# top_power.net
KiCad netlist of a schematic drawn in Altium Designer
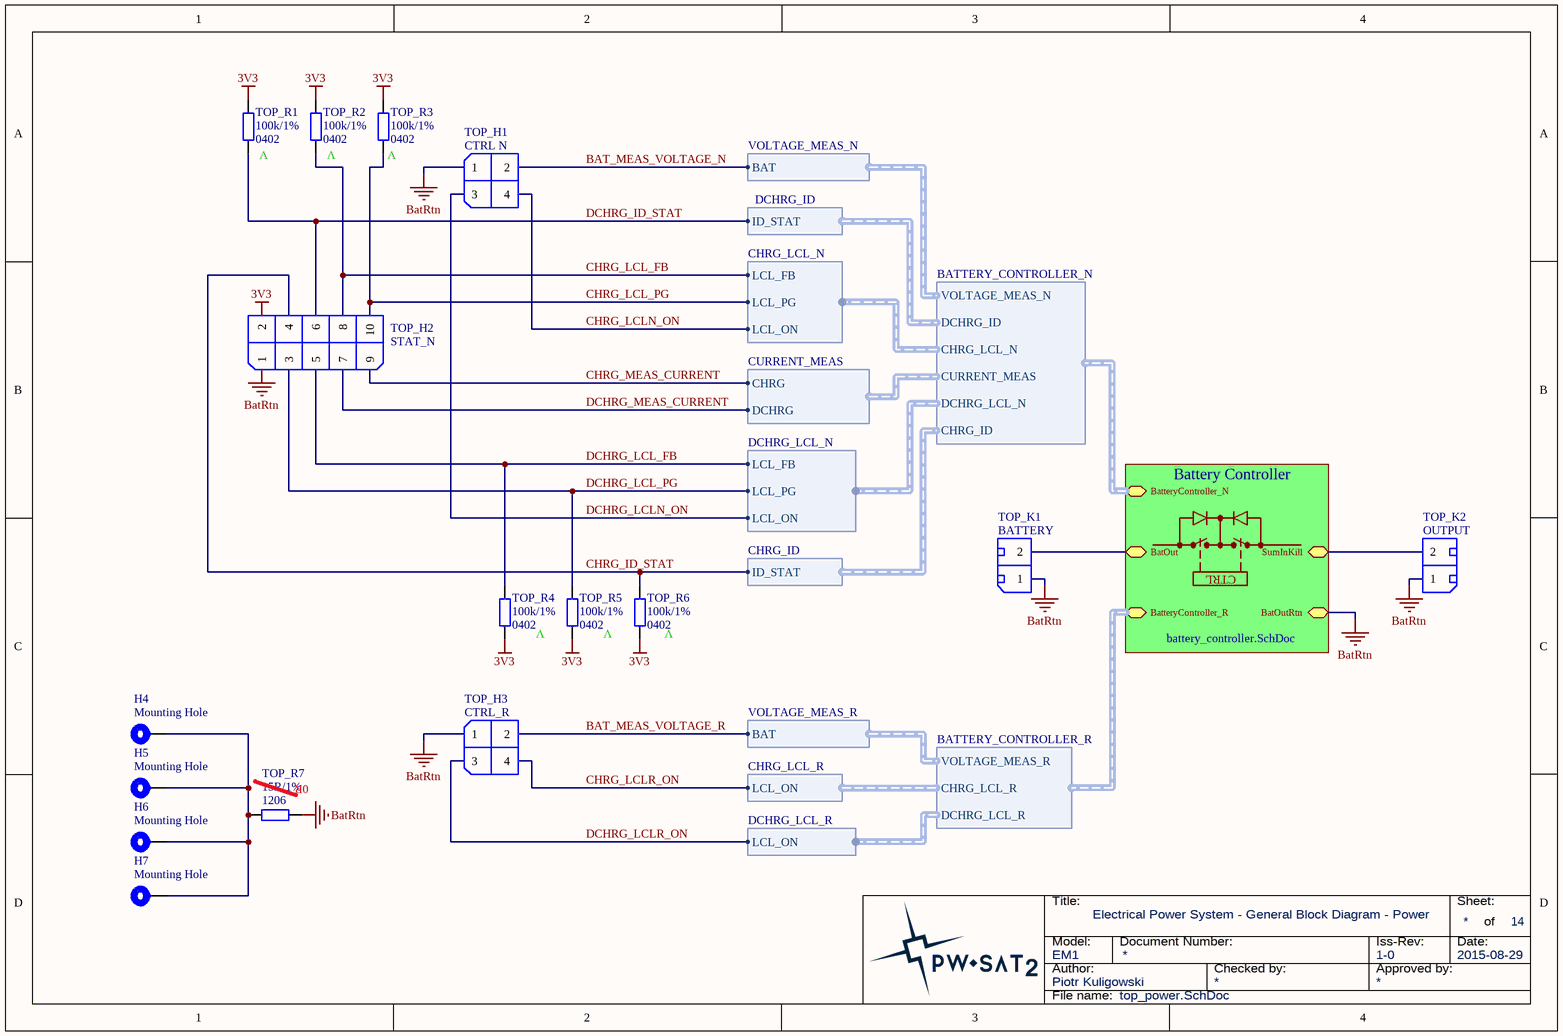
[diagram p0: top_power.SchDoc]

(export (version "E")
  (design (tool "Eeschema 10.0.6"))
  (components
    (comp (ref "H4")
      (value "Mounting Hole")
      (footprint "PC-104_PcbMntHole_M3")
      (description "PCB Mounting Hole")
      (libsource (lib "connectors_printed-circuit-board") (part "MntHole"))
    )
    (comp (ref "H5")
      (value "Mounting Hole")
      (footprint "PC-104_PcbMntHole_M3")
      (description "PCB Mounting Hole")
      (libsource (lib "connectors_printed-circuit-board") (part "MntHole"))
    )
    (comp (ref "H6")
      (value "Mounting Hole")
      (footprint "PC-104_PcbMntHole_M3")
      (description "PCB Mounting Hole")
      (libsource (lib "connectors_printed-circuit-board") (part "MntHole"))
    )
    (comp (ref "H7")
      (value "Mounting Hole")
      (footprint "PC-104_PcbMntHole_M3")
      (description "PCB Mounting Hole")
      (libsource (lib "connectors_printed-circuit-board") (part "MntHole"))
    )
    (comp (ref "TOP_H1")
      (value "CTRL N")
      (footprint "Harwin_Datamate_L-Tek_M80-8670405")
      (description "Harwin DataMate L-Tek, 2mm pitch, 2x2pin.")
      (libsource (lib "connectors_printed-circuit-board") (part "Harwin_Datamate_L-Tek_2x2pin"))
    )
    (comp (ref "TOP_H2")
      (value "STAT_N")
      (footprint "Harwin_Datamate_L-Tek_M80-8671005")
      (description "Harwin DataMate L-Tek, 2mm pitch, 2x5pin.")
      (libsource (lib "connectors_printed-circuit-board") (part "Harwin_Datamate_L-Tek_2x5pin"))
    )
    (comp (ref "TOP_H3")
      (value "CTRL_R")
      (footprint "Harwin_Datamate_L-Tek_M80-8670405")
      (description "Harwin DataMate L-Tek, 2mm pitch, 2x2pin.")
      (libsource (lib "connectors_printed-circuit-board") (part "Harwin_Datamate_L-Tek_2x2pin"))
    )
    (comp (ref "TOP_K1")
      (value "TB-2.5-PD-xx")
      (footprint "TerminalBlock_Spring_2.54_2-R")
      (description "Terminal block with spring, 2-pin, 2.54mm pitch, right angle.")
      (fields (field (name "PROVIDERPARTNUMBER") "BATTERY") (field (name "PROVIDER") "TME.eu"))
      (libsource (lib "connectors_printed-circuit-board") (part "TerminalBlock_Spring_2.54_2-R"))
    )
    (comp (ref "TOP_K2")
      (value "TB-2.5-PD-xx")
      (footprint "TerminalBlock_Spring_2.54_2-R")
      (description "Terminal block with spring, 2-pin, 2.54mm pitch, right angle.")
      (fields (field (name "PROVIDERPARTNUMBER") "OUTPUT") (field (name "PROVIDER") "TME.eu"))
      (libsource (lib "connectors_printed-circuit-board") (part "TerminalBlock_Spring_2.54_2-R"))
    )
    (comp (ref "TOP_R1")
      (value "100k/1%")
      (footprint "SMD_Resistor_0402")
      (description "100k/1% Vishay CRCW 0402 Resistor. 63mW, 100ppm, 50V.")
      (fields (field (name "MANUFACTURER") "Vishay") (field (name "PACKAGE") "0402"))
      (libsource (lib "resistors") (part "CRCW0402100KFKxxxx"))
    )
    (comp (ref "TOP_R2")
      (value "100k/1%")
      (footprint "SMD_Resistor_0402")
      (description "100k/1% Vishay CRCW 0402 Resistor. 63mW, 100ppm, 50V.")
      (fields (field (name "MANUFACTURER") "Vishay") (field (name "PACKAGE") "0402"))
      (libsource (lib "resistors") (part "CRCW0402100KFKxxxx"))
    )
    (comp (ref "TOP_R3")
      (value "100k/1%")
      (footprint "SMD_Resistor_0402")
      (description "100k/1% Vishay CRCW 0402 Resistor. 63mW, 100ppm, 50V.")
      (fields (field (name "MANUFACTURER") "Vishay") (field (name "PACKAGE") "0402"))
      (libsource (lib "resistors") (part "CRCW0402100KFKxxxx"))
    )
    (comp (ref "TOP_R4")
      (value "100k/1%")
      (footprint "SMD_Resistor_0402")
      (description "100k/1% Vishay CRCW 0402 Resistor. 63mW, 100ppm, 50V.")
      (fields (field (name "MANUFACTURER") "Vishay") (field (name "PACKAGE") "0402"))
      (libsource (lib "resistors") (part "CRCW0402100KFKxxxx"))
    )
    (comp (ref "TOP_R5")
      (value "100k/1%")
      (footprint "SMD_Resistor_0402")
      (description "100k/1% Vishay CRCW 0402 Resistor. 63mW, 100ppm, 50V.")
      (fields (field (name "MANUFACTURER") "Vishay") (field (name "PACKAGE") "0402"))
      (libsource (lib "resistors") (part "CRCW0402100KFKxxxx"))
    )
    (comp (ref "TOP_R6")
      (value "100k/1%")
      (footprint "SMD_Resistor_0402")
      (description "100k/1% Vishay CRCW 0402 Resistor. 63mW, 100ppm, 50V.")
      (fields (field (name "MANUFACTURER") "Vishay") (field (name "PACKAGE") "0402"))
      (libsource (lib "resistors") (part "CRCW0402100KFKxxxx"))
    )
    (comp (ref "TOP_R7")
      (value "15R/1%")
      (footprint "SMD_Resistor_1206")
      (description "15R/1% Vishay CRCW 1206 Resistor. 250mW, 100ppm, 200V.")
      (fields
        (field (name "MANUFACTURERPARTNUMBER") "CRCW120615R0FKxxxx")
        (field (name "MANUFACTURER") "Vishay")
        (field (name "PACKAGE") "1206")
      )
      (libsource (lib "resistors") (part "CRCW120615R0FKxxxx"))
    )
  )
  (nets
    (net (code "10") (name "/BAT_MEAS_VOLTAGE_N") (class "Default")
      (node (ref "TOP_H1") (pin "2") (pinfunction "2_2") (pintype "passive"))
    )
    (net (code "11") (name "/BAT_MEAS_VOLTAGE_R") (class "Default")
      (node (ref "TOP_H3") (pin "2") (pinfunction "2_2") (pintype "passive"))
    )
    (net (code "12") (name "/BatOut") (class "Default")
      (node (ref "TOP_K1") (pin "2") (pinfunction "2_2") (pintype "passive"))
    )
    (net (code "15") (name "/CHRG_ID_STAT") (class "Default")
      (node (ref "TOP_H2") (pin "4") (pinfunction "4_4") (pintype "passive"))
      (node (ref "TOP_R6") (pin "1") (pinfunction "1_1") (pintype "passive"))
    )
    (net (code "16") (name "/CHRG_LCLN_ON") (class "Default")
      (node (ref "TOP_H1") (pin "4") (pinfunction "4_4") (pintype "passive"))
    )
    (net (code "17") (name "/CHRG_LCLR_ON") (class "Default")
      (node (ref "TOP_H3") (pin "4") (pinfunction "4_4") (pintype "passive"))
    )
    (net (code "18") (name "/CHRG_LCL_FB") (class "Default")
      (node (ref "TOP_H2") (pin "8") (pinfunction "8_8") (pintype "passive"))
      (node (ref "TOP_R2") (pin "2") (pinfunction "2_2") (pintype "passive"))
    )
    (net (code "19") (name "/CHRG_LCL_PG") (class "Default")
      (node (ref "TOP_H2") (pin "10") (pinfunction "10_10") (pintype "passive"))
      (node (ref "TOP_R3") (pin "2") (pinfunction "2_2") (pintype "passive"))
    )
    (net (code "20") (name "/CHRG_MEAS_CURRENT") (class "Default")
      (node (ref "TOP_H2") (pin "9") (pinfunction "9_9") (pintype "passive"))
    )
    (net (code "21") (name "/DCHRG_ID_STAT") (class "Default")
      (node (ref "TOP_H2") (pin "6") (pinfunction "6_6") (pintype "passive"))
      (node (ref "TOP_R1") (pin "2") (pinfunction "2_2") (pintype "passive"))
    )
    (net (code "22") (name "/DCHRG_LCLN_ON") (class "Default")
      (node (ref "TOP_H1") (pin "3") (pinfunction "3_3") (pintype "passive"))
    )
    (net (code "23") (name "/DCHRG_LCLR_ON") (class "Default")
      (node (ref "TOP_H3") (pin "3") (pinfunction "3_3") (pintype "passive"))
    )
    (net (code "24") (name "/DCHRG_LCL_FB") (class "Default")
      (node (ref "TOP_H2") (pin "5") (pinfunction "5_5") (pintype "passive"))
      (node (ref "TOP_R4") (pin "1") (pinfunction "1_1") (pintype "passive"))
    )
    (net (code "25") (name "/DCHRG_LCL_PG") (class "Default")
      (node (ref "TOP_H2") (pin "3") (pinfunction "3_3") (pintype "passive"))
      (node (ref "TOP_R5") (pin "1") (pinfunction "1_1") (pintype "passive"))
    )
    (net (code "26") (name "/DCHRG_MEAS_CURRENT") (class "Default")
      (node (ref "TOP_H2") (pin "7") (pinfunction "7_7") (pintype "passive"))
    )
    (net (code "27") (name "/SumInKill") (class "Default")
      (node (ref "TOP_K2") (pin "2") (pinfunction "2_2") (pintype "passive"))
    )
    (net (code "37") (name "3V3") (class "Default")
      (node (ref "TOP_H2") (pin "2") (pinfunction "2_2") (pintype "passive"))
      (node (ref "TOP_R1") (pin "1") (pinfunction "1_1") (pintype "passive"))
      (node (ref "TOP_R2") (pin "1") (pinfunction "1_1") (pintype "passive"))
      (node (ref "TOP_R3") (pin "1") (pinfunction "1_1") (pintype "passive"))
      (node (ref "TOP_R4") (pin "2") (pinfunction "2_2") (pintype "passive"))
      (node (ref "TOP_R5") (pin "2") (pinfunction "2_2") (pintype "passive"))
      (node (ref "TOP_R6") (pin "2") (pinfunction "2_2") (pintype "passive"))
    )
    (net (code "38") (name "BatRtn") (class "Default")
      (node (ref "TOP_H1") (pin "1") (pinfunction "1_1") (pintype "passive"))
      (node (ref "TOP_H2") (pin "1") (pinfunction "1_1") (pintype "passive"))
      (node (ref "TOP_H3") (pin "1") (pinfunction "1_1") (pintype "passive"))
      (node (ref "TOP_K1") (pin "1") (pinfunction "1_1") (pintype "passive"))
      (node (ref "TOP_K2") (pin "1") (pinfunction "1_1") (pintype "passive"))
      (node (ref "TOP_R7") (pin "2") (pinfunction "2_2") (pintype "passive"))
    )
    (net (code "39") (name "Net-(H4-Pad1)") (class "Default")
      (node (ref "H4") (pin "1") (pinfunction "1_1") (pintype "passive"))
      (node (ref "H5") (pin "1") (pinfunction "1_1") (pintype "passive"))
      (node (ref "H6") (pin "1") (pinfunction "1_1") (pintype "passive"))
      (node (ref "H7") (pin "1") (pinfunction "1_1") (pintype "passive"))
      (node (ref "TOP_R7") (pin "1") (pinfunction "1_1") (pintype "passive"))
    )
  )
)
